# LoraWAN_Node.net
KiCad netlist of a schematic drawn in Altium Designer
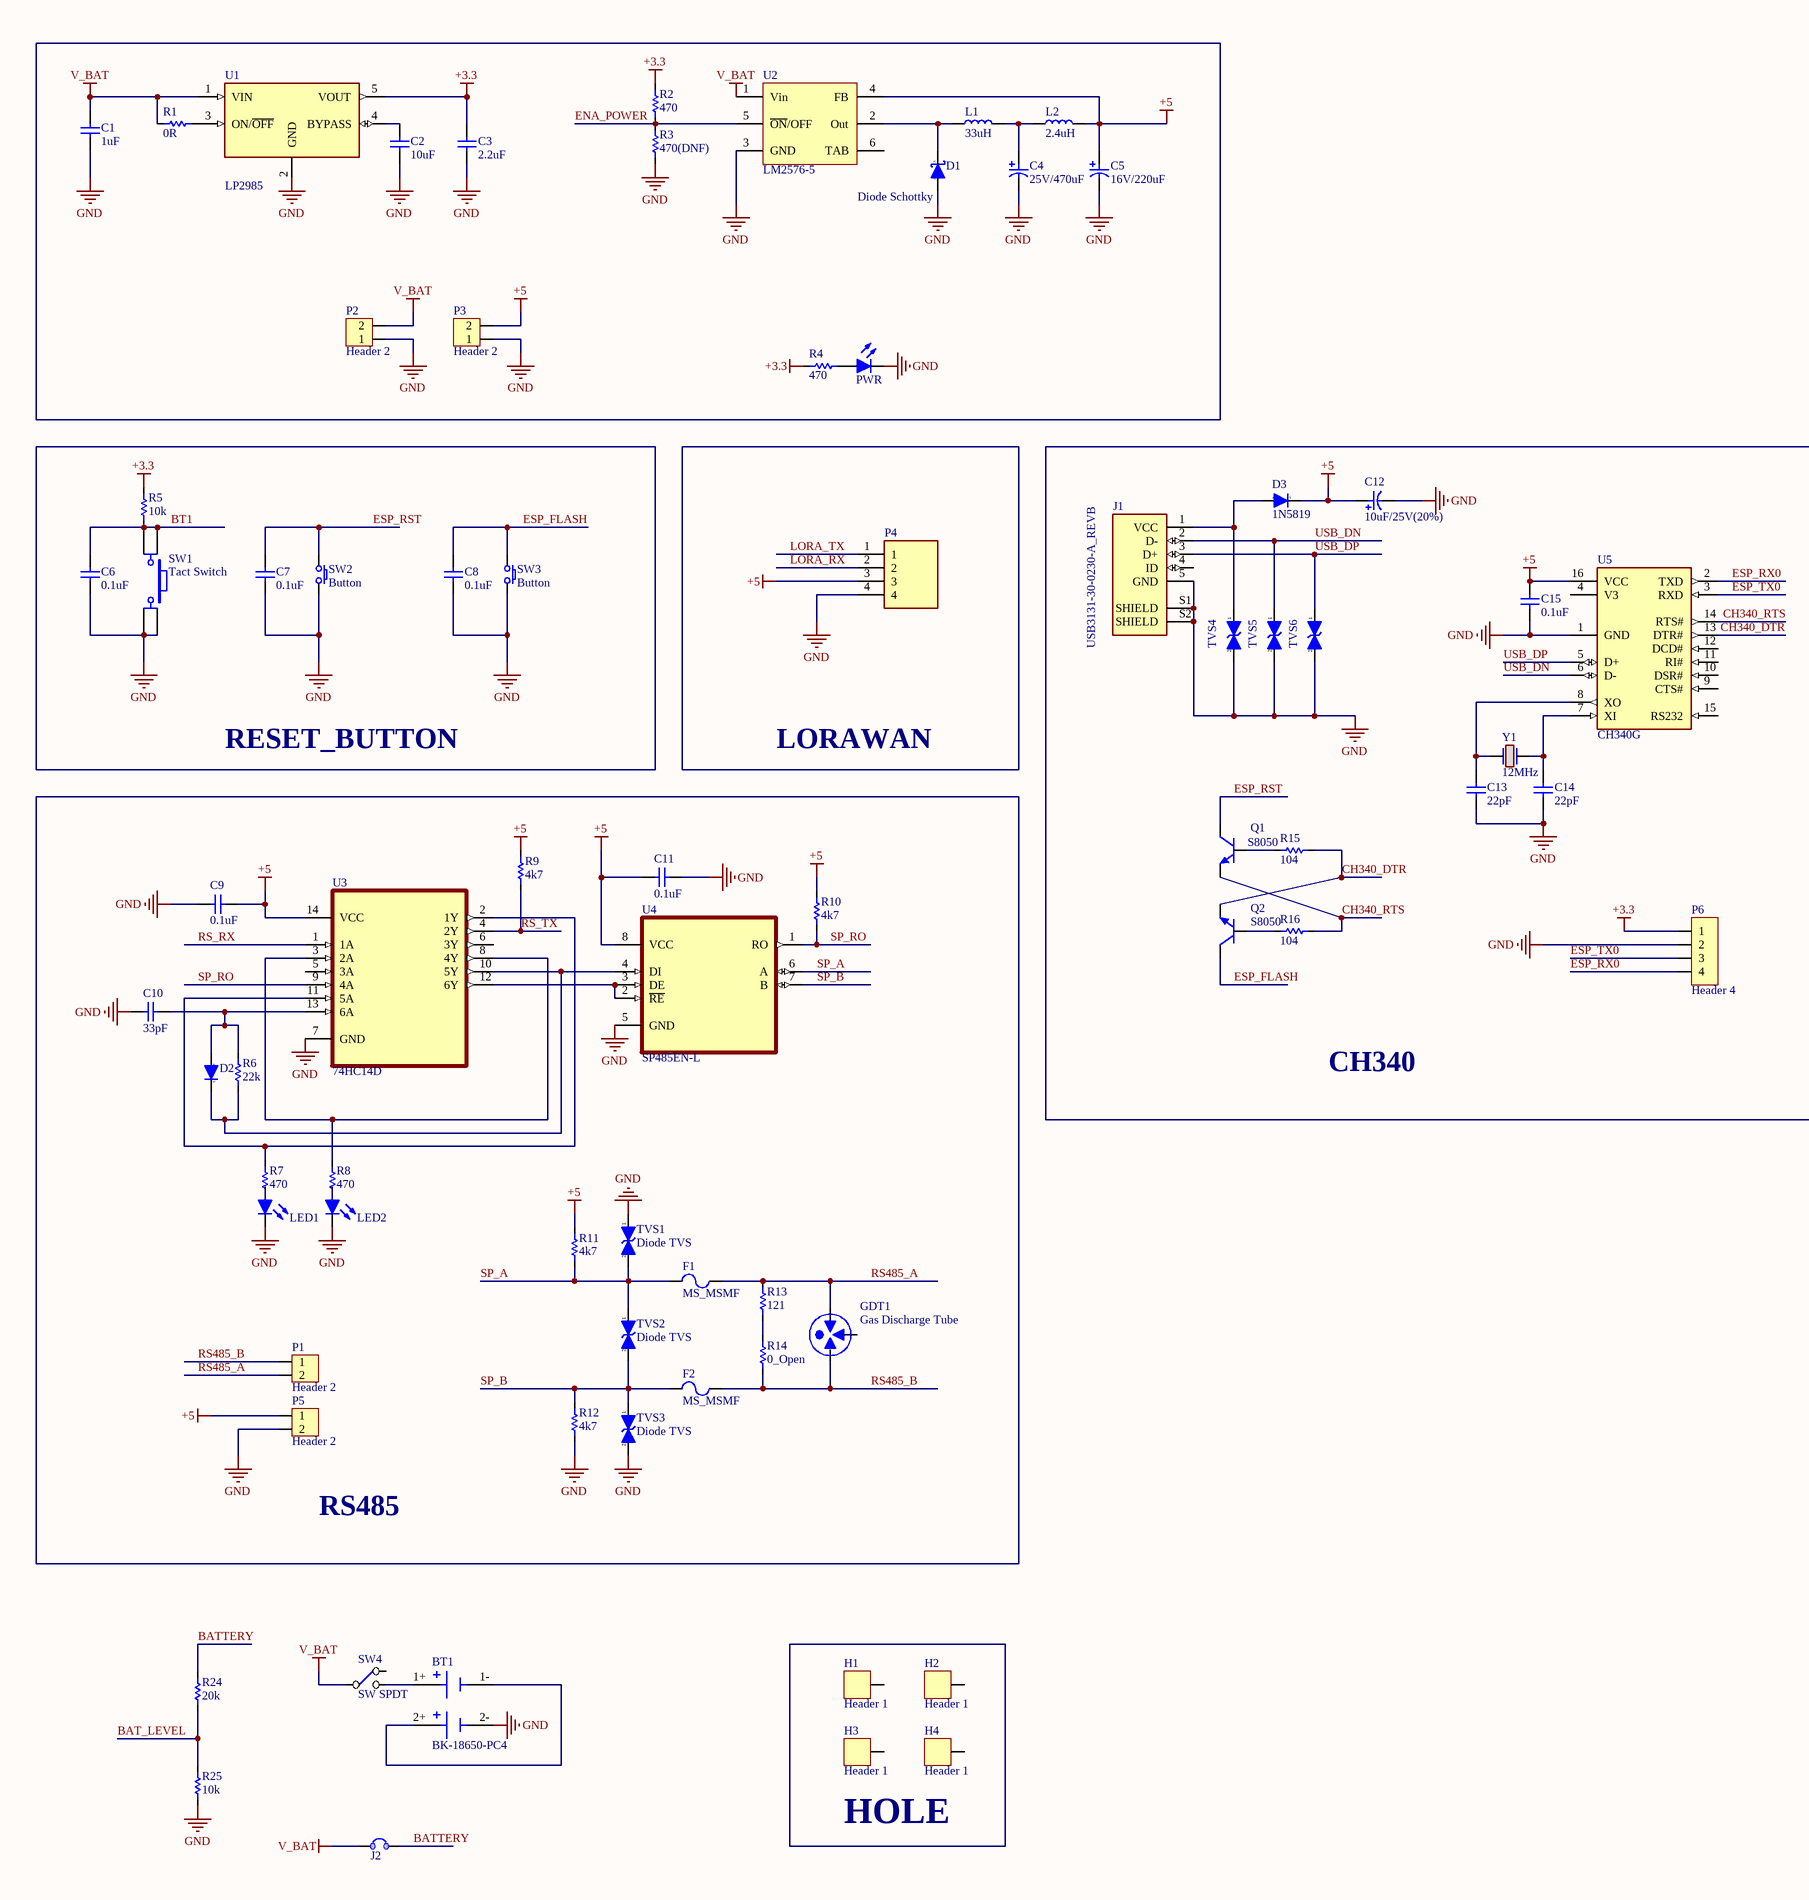
[diagram p0: LoraWAN_Node.SchDoc, left]
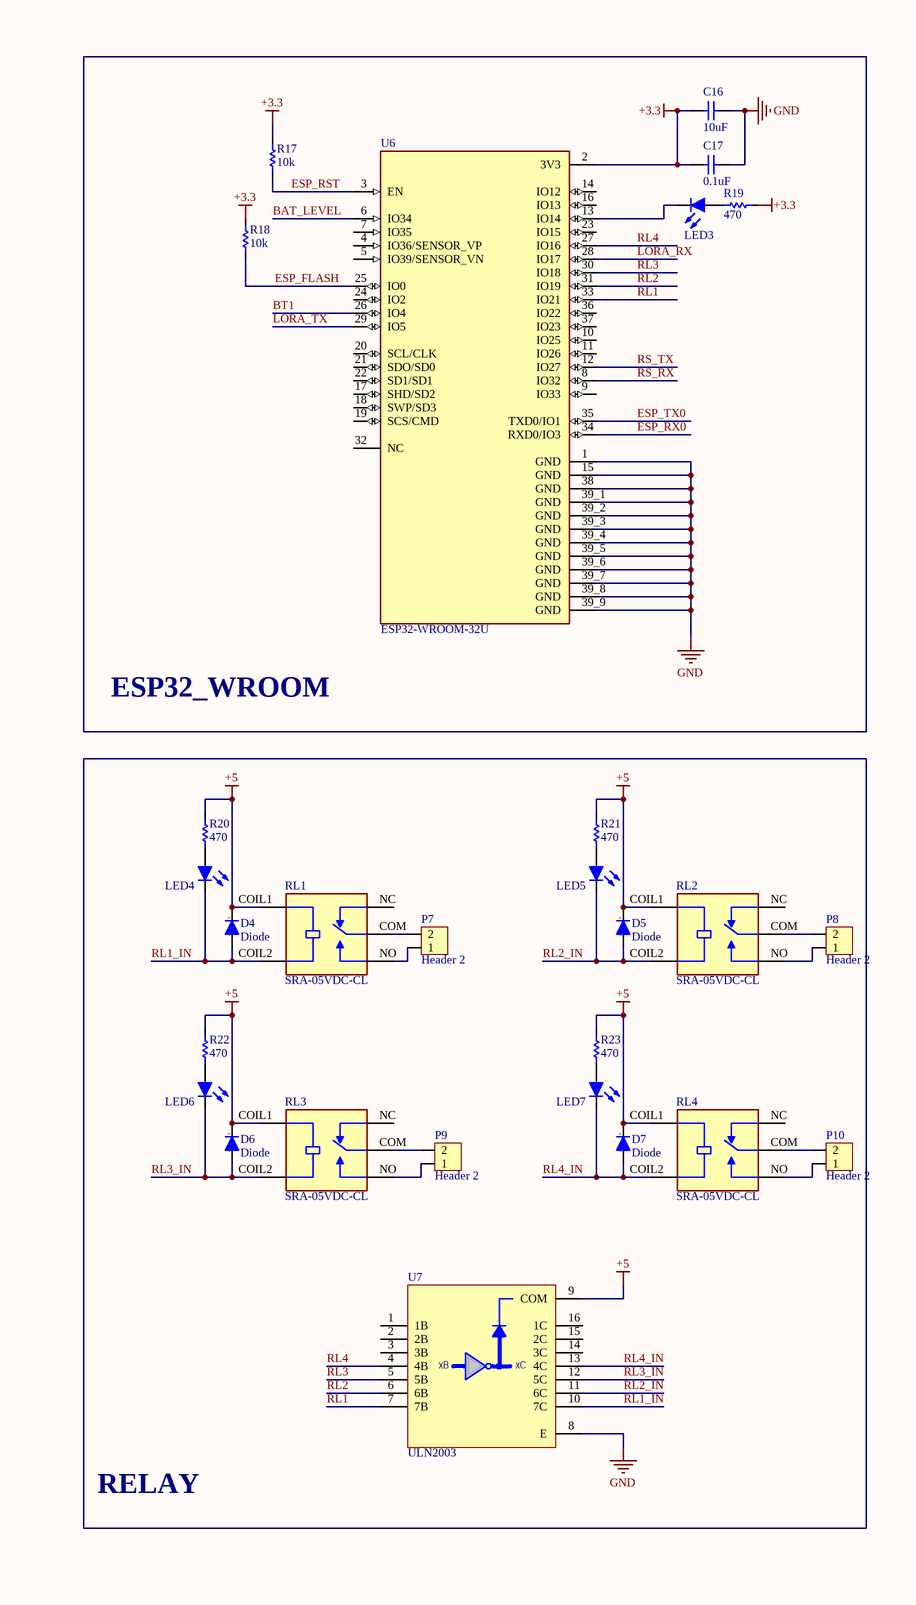
[diagram p1: LoraWAN_Node.SchDoc, right]

(export (version "E")
  (design (tool "Eeschema 10.0.6"))
  (components
    (comp (ref "BT1")
      (value "BK-18650-PC4")
      (footprint "BAT_BK-18650-PC4")
      (description "Battery Holder (Open) 18650 2 Cell PC Pin")
      (libsource (lib "BK-18650-PC4") (part "BK-18650-PC4"))
    )
    (comp (ref "C1")
      (value "1uF")
      (footprint "C 0603 (1608)")
      (description "Capacitor non-pol")
      (libsource (lib "BKIT4U_LIB_NEW") (part "Capacitor NP"))
    )
    (comp (ref "C2")
      (value "10uF")
      (footprint "C 0603 (1608)")
      (description "Capacitor non-pol")
      (libsource (lib "BKIT4U_LIB_NEW") (part "Capacitor NP"))
    )
    (comp (ref "C3")
      (value "2.2uF")
      (footprint "C 0603 (1608)")
      (description "Capacitor non-pol")
      (libsource (lib "BKIT4U_LIB_NEW") (part "Capacitor NP"))
    )
    (comp (ref "C4")
      (value "25V/470uF")
      (footprint "C SMD ALU (G)")
      (description "Capacitor pol")
      (libsource (lib "BKIT4U_LIB_NEW") (part "Capacitor"))
    )
    (comp (ref "C5")
      (value "16V/220uF")
      (footprint "C SMD ALU (D8)")
      (description "Capacitor pol")
      (libsource (lib "BKIT4U_LIB_NEW") (part "Capacitor"))
    )
    (comp (ref "C6")
      (value "0.1uF")
      (footprint "C 0603 (1608)")
      (description "Capacitor non-pol")
      (libsource (lib "BKIT4U_LIB_NEW") (part "Capacitor NP"))
    )
    (comp (ref "C7")
      (value "0.1uF")
      (footprint "C 0603 (1608)")
      (description "Capacitor non-pol")
      (libsource (lib "BKIT4U_LIB_NEW") (part "Capacitor NP"))
    )
    (comp (ref "C8")
      (value "0.1uF")
      (footprint "C 0603 (1608)")
      (description "Capacitor non-pol")
      (libsource (lib "BKIT4U_LIB_NEW") (part "Capacitor NP"))
    )
    (comp (ref "C9")
      (value "0.1uF")
      (footprint "C 0603 (1608)")
      (description "Capacitor non-pol")
      (libsource (lib "BKIT4U_LIB_NEW") (part "Capacitor NP"))
    )
    (comp (ref "C10")
      (value "33pF")
      (footprint "C 0603 (1608)")
      (description "Capacitor non-pol")
      (libsource (lib "BKIT4U_LIB_NEW") (part "Capacitor NP"))
    )
    (comp (ref "C11")
      (value "0.1uF")
      (footprint "C 0603 (1608)")
      (description "Capacitor non-pol")
      (libsource (lib "BKIT4U_LIB_NEW") (part "Capacitor NP"))
    )
    (comp (ref "C12")
      (value "10uF/25V(20%)")
      (footprint "C SMD TAN 1206 (A)")
      (description "Capacitor pol")
      (libsource (lib "BKIT4U_LIB_NEW") (part "Capacitor"))
    )
    (comp (ref "C13")
      (value "22pF")
      (footprint "C 0603 (1608)")
      (description "Capacitor non-pol")
      (libsource (lib "BKIT4U_LIB_NEW") (part "Capacitor NP"))
    )
    (comp (ref "C14")
      (value "22pF")
      (footprint "C 0603 (1608)")
      (description "Capacitor non-pol")
      (libsource (lib "BKIT4U_LIB_NEW") (part "Capacitor NP"))
    )
    (comp (ref "C15")
      (value "0.1uF")
      (footprint "C 0603 (1608)")
      (description "Capacitor non-pol")
      (libsource (lib "BKIT4U_LIB_NEW") (part "Capacitor NP"))
    )
    (comp (ref "C16")
      (value "10uF")
      (footprint "C 0603 (1608)")
      (description "Capacitor non-pol")
      (libsource (lib "BKIT4U_LIB_NEW") (part "Capacitor NP"))
    )
    (comp (ref "C17")
      (value "0.1uF")
      (footprint "C 0603 (1608)")
      (description "Capacitor non-pol")
      (libsource (lib "BKIT4U_LIB_NEW") (part "Capacitor NP"))
    )
    (comp (ref "D1")
      (value "Diode Schottky")
      (footprint "DO-214AC (SMA)")
      (description "Schottky Diode")
      (libsource (lib "BKIT4U_LIB_NEW") (part "Diode Schottky"))
    )
    (comp (ref "D2")
      (value "Diode")
      (footprint "DO-214AC (SMA)")
      (description "Default Diode")
      (libsource (lib "BKIT4U_LIB_NEW") (part "Diode"))
    )
    (comp (ref "D3")
      (value "1N5819")
      (footprint "DO-214AC (SMA)")
      (description "Default Diode")
      (libsource (lib "BKIT4U_LIB_NEW") (part "Diode"))
    )
    (comp (ref "D4")
      (value "Diode")
      (footprint "DO-214AC (SMA)")
      (description "Default Diode")
      (libsource (lib "BKIT4U_LIB_NEW") (part "Diode"))
    )
    (comp (ref "D5")
      (value "Diode")
      (footprint "DO-214AC (SMA)")
      (description "Default Diode")
      (libsource (lib "BKIT4U_LIB_NEW") (part "Diode"))
    )
    (comp (ref "D6")
      (value "Diode")
      (footprint "DO-214AC (SMA)")
      (description "Default Diode")
      (libsource (lib "BKIT4U_LIB_NEW") (part "Diode"))
    )
    (comp (ref "D7")
      (value "Diode")
      (footprint "DO-214AC (SMA)")
      (description "Default Diode")
      (libsource (lib "BKIT4U_LIB_NEW") (part "Diode"))
    )
    (comp (ref "F1")
      (value "MS_MSMF")
      (footprint "Fuse 1812P050")
      (description "Fuse")
      (libsource (lib "BKIT4U_LIB_NEW") (part "Fuse"))
    )
    (comp (ref "F2")
      (value "MS_MSMF")
      (footprint "Fuse 1812P050")
      (description "Fuse")
      (libsource (lib "BKIT4U_LIB_NEW") (part "Fuse"))
    )
    (comp (ref "GDT1")
      (value "Gas Discharge Tube")
      (footprint "CAPC4532X110N")
      (libsource (lib "BKIT4U_LIB_NEW") (part "Gas Discharge Tube"))
    )
    (comp (ref "H1")
      (value "Header 1")
      (footprint "M3")
      (description "Header, 1-Pin")
      (libsource (lib "BKIT4U_LIB_NEW") (part "Header 1"))
    )
    (comp (ref "H2")
      (value "Header 1")
      (footprint "M3")
      (description "Header, 1-Pin")
      (libsource (lib "BKIT4U_LIB_NEW") (part "Header 1"))
    )
    (comp (ref "H3")
      (value "Header 1")
      (footprint "M3")
      (description "Header, 1-Pin")
      (libsource (lib "BKIT4U_LIB_NEW") (part "Header 1"))
    )
    (comp (ref "H4")
      (value "Header 1")
      (footprint "M3")
      (description "Header, 1-Pin")
      (libsource (lib "BKIT4U_LIB_NEW") (part "Header 1"))
    )
    (comp (ref "J1")
      (value "USB3131-30-0230-A_REVB")
      (footprint "GCT_USB3131-30-0230-A_REVB")
      (description "USB - micro B USB 2.0 Receptacle Connector 5 Position Through Hole")
      (libsource (lib "USB3131-30-0230-A_REVB") (part "USB3131-30-0230-A_REVB"))
    )
    (comp (ref "J2")
      (value "JUMP 2")
      (footprint "JUMP/2/SMD/D")
      (libsource (lib "chipfc_altium_libs") (part "JUMP 2"))
    )
    (comp (ref "L1")
      (value "33uH")
      (footprint "Inductor SMD 12x12x8")
      (description "Inductor")
      (libsource (lib "BKIT4U_LIB_NEW") (part "Inductor"))
    )
    (comp (ref "L2")
      (value "2.4uH")
      (footprint "Inductor SMD 5.2x5.8x4.5mm")
      (description "Inductor")
      (libsource (lib "BKIT4U_LIB_NEW") (part "Inductor"))
    )
    (comp (ref "LED1")
      (value "Led")
      (footprint "Led SMD 0805")
      (description "Typical LED")
      (libsource (lib "BKIT4U_LIB_NEW") (part "Led"))
    )
    (comp (ref "LED2")
      (value "Led")
      (footprint "Led SMD 0805")
      (description "Typical LED")
      (libsource (lib "BKIT4U_LIB_NEW") (part "Led"))
    )
    (comp (ref "LED3")
      (value "Led")
      (footprint "Led SMD 0805")
      (description "Typical LED")
      (libsource (lib "BKIT4U_LIB_NEW") (part "Led"))
    )
    (comp (ref "LED4")
      (value "Led")
      (footprint "Led SMD 0805")
      (description "Typical LED")
      (libsource (lib "BKIT4U_LIB_NEW") (part "Led"))
    )
    (comp (ref "LED5")
      (value "Led")
      (footprint "Led SMD 0805")
      (description "Typical LED")
      (libsource (lib "BKIT4U_LIB_NEW") (part "Led"))
    )
    (comp (ref "LED6")
      (value "Led")
      (footprint "Led SMD 0805")
      (description "Typical LED")
      (libsource (lib "BKIT4U_LIB_NEW") (part "Led"))
    )
    (comp (ref "LED7")
      (value "Led")
      (footprint "Led SMD 0805")
      (description "Typical LED")
      (libsource (lib "BKIT4U_LIB_NEW") (part "Led"))
    )
    (comp (ref "P1")
      (value "Header 2")
      (footprint "HDR Domino 2 - 5MM")
      (description "Header, 2-Pin")
      (libsource (lib "") (part "Header 2_2"))
    )
    (comp (ref "P2")
      (value "Header 2")
      (footprint "HDR Domino 2 - 5MM")
      (description "Header, 2-Pin")
      (libsource (lib "BKIT4U_LIB_NEW") (part "Header 2"))
    )
    (comp (ref "P3")
      (value "Header 2")
      (footprint "HDR Domino 2 - 5MM")
      (description "Header, 2-Pin")
      (libsource (lib "BKIT4U_LIB_NEW") (part "Header 2"))
    )
    (comp (ref "P4")
      (value "110990030")
      (footprint "SEEED_110990030")
      (fields (field (name "MF") "Seeed Technology"))
      (libsource (lib "110990030") (part "110990030"))
    )
    (comp (ref "P5")
      (value "Header 2")
      (footprint "HDR Domino 2 - 5MM")
      (description "Header, 2-Pin")
      (libsource (lib "") (part "Header 2_2"))
    )
    (comp (ref "P6")
      (value "Header 4")
      (footprint "Header 4")
      (description "Header, 4-Pin")
      (libsource (lib "BKIT4U_LIB_NEW") (part "Header 4"))
    )
    (comp (ref "P7")
      (value "Header 2")
      (footprint "HDR Domino 2 - 5MM")
      (description "Header, 2-Pin")
      (libsource (lib "") (part "Header 2_1"))
    )
    (comp (ref "P8")
      (value "Header 2")
      (footprint "HDR Domino 2 - 5MM")
      (description "Header, 2-Pin")
      (libsource (lib "") (part "Header 2_1"))
    )
    (comp (ref "P9")
      (value "Header 2")
      (footprint "HDR Domino 2 - 5MM")
      (description "Header, 2-Pin")
      (libsource (lib "") (part "Header 2_1"))
    )
    (comp (ref "P10")
      (value "Header 2")
      (footprint "HDR Domino 2 - 5MM")
      (description "Header, 2-Pin")
      (libsource (lib "") (part "Header 2_1"))
    )
    (comp (ref "PWR")
      (value "Led")
      (footprint "Led SMD 0805")
      (description "Typical LED")
      (libsource (lib "BKIT4U_LIB_NEW") (part "Led"))
    )
    (comp (ref "Q1")
      (value "S8050")
      (footprint "SOT-23")
      (description "NPN Bipolar Transistor")
      (libsource (lib "BKIT4U_LIB_NEW") (part "Transistor NPN"))
    )
    (comp (ref "Q2")
      (value "S8050")
      (footprint "SOT-23")
      (description "NPN Bipolar Transistor")
      (libsource (lib "BKIT4U_LIB_NEW") (part "Transistor NPN"))
    )
    (comp (ref "R1")
      (value "0R")
      (footprint "R 0603 (1608)")
      (description "Resistor")
      (libsource (lib "BKIT4U_LIB_NEW") (part "Resistor"))
    )
    (comp (ref "R2")
      (value "470")
      (footprint "R 0603 (1608)")
      (description "Resistor")
      (libsource (lib "BKIT4U_LIB_NEW") (part "Resistor"))
    )
    (comp (ref "R3")
      (value "470(DNF)")
      (footprint "R 0603 (1608)")
      (description "Resistor")
      (libsource (lib "BKIT4U_LIB_NEW") (part "Resistor"))
    )
    (comp (ref "R4")
      (value "470")
      (footprint "R 0603 (1608)")
      (description "Resistor")
      (libsource (lib "BKIT4U_LIB_NEW") (part "Resistor"))
    )
    (comp (ref "R5")
      (value "10k")
      (footprint "R 0603 (1608)")
      (description "Resistor")
      (libsource (lib "BKIT4U_LIB_NEW") (part "Resistor"))
    )
    (comp (ref "R6")
      (value "22k")
      (footprint "R 0603 (1608)")
      (description "Resistor")
      (libsource (lib "BKIT4U_LIB_NEW") (part "Resistor"))
    )
    (comp (ref "R7")
      (value "470")
      (footprint "R 0603 (1608)")
      (description "Resistor")
      (libsource (lib "BKIT4U_LIB_NEW") (part "Resistor"))
    )
    (comp (ref "R8")
      (value "470")
      (footprint "R 0603 (1608)")
      (description "Resistor")
      (libsource (lib "BKIT4U_LIB_NEW") (part "Resistor"))
    )
    (comp (ref "R9")
      (value "4k7")
      (footprint "R 0603 (1608)")
      (description "Resistor")
      (libsource (lib "BKIT4U_LIB_NEW") (part "Resistor"))
    )
    (comp (ref "R10")
      (value "4k7")
      (footprint "R 0603 (1608)")
      (description "Resistor")
      (libsource (lib "BKIT4U_LIB_NEW") (part "Resistor"))
    )
    (comp (ref "R11")
      (value "4k7")
      (footprint "R 0603 (1608)")
      (description "Resistor")
      (libsource (lib "BKIT4U_LIB_NEW") (part "Resistor"))
    )
    (comp (ref "R12")
      (value "4k7")
      (footprint "R 0603 (1608)")
      (description "Resistor")
      (libsource (lib "BKIT4U_LIB_NEW") (part "Resistor"))
    )
    (comp (ref "R13")
      (value "121")
      (footprint "R 0603 (1608)")
      (description "Resistor")
      (libsource (lib "BKIT4U_LIB_NEW") (part "Resistor"))
    )
    (comp (ref "R14")
      (value "0_Open")
      (footprint "R 0603 (1608)")
      (description "Resistor")
      (libsource (lib "BKIT4U_LIB_NEW") (part "Resistor"))
    )
    (comp (ref "R15")
      (value "104")
      (footprint "R 0603 (1608)")
      (description "Resistor")
      (libsource (lib "BKIT4U_LIB_NEW") (part "Resistor"))
    )
    (comp (ref "R16")
      (value "104")
      (footprint "R 0603 (1608)")
      (description "Resistor")
      (libsource (lib "BKIT4U_LIB_NEW") (part "Resistor"))
    )
    (comp (ref "R17")
      (value "10k")
      (footprint "R 0603 (1608)")
      (description "Resistor")
      (libsource (lib "BKIT4U_LIB_NEW") (part "Resistor"))
    )
    (comp (ref "R18")
      (value "10k")
      (footprint "R 0603 (1608)")
      (description "Resistor")
      (libsource (lib "BKIT4U_LIB_NEW") (part "Resistor"))
    )
    (comp (ref "R19")
      (value "470")
      (footprint "R 0603 (1608)")
      (description "Resistor")
      (libsource (lib "BKIT4U_LIB_NEW") (part "Resistor"))
    )
    (comp (ref "R20")
      (value "470")
      (footprint "R 0603 (1608)")
      (description "Resistor")
      (libsource (lib "BKIT4U_LIB_NEW") (part "Resistor"))
    )
    (comp (ref "R21")
      (value "470")
      (footprint "R 0603 (1608)")
      (description "Resistor")
      (libsource (lib "BKIT4U_LIB_NEW") (part "Resistor"))
    )
    (comp (ref "R22")
      (value "470")
      (footprint "R 0603 (1608)")
      (description "Resistor")
      (libsource (lib "BKIT4U_LIB_NEW") (part "Resistor"))
    )
    (comp (ref "R23")
      (value "470")
      (footprint "R 0603 (1608)")
      (description "Resistor")
      (libsource (lib "BKIT4U_LIB_NEW") (part "Resistor"))
    )
    (comp (ref "R24")
      (value "20k")
      (footprint "R 0603 (1608)")
      (description "Resistor")
      (libsource (lib "BKIT4U_LIB_NEW") (part "Resistor"))
    )
    (comp (ref "R25")
      (value "10k")
      (footprint "R 0603 (1608)")
      (description "Resistor")
      (libsource (lib "BKIT4U_LIB_NEW") (part "Resistor"))
    )
    (comp (ref "RL1")
      (value "SRA-05VDC-CL")
      (footprint "RELAY_SRA-05VDC-CL")
      (fields (field (name "MF") "Songle Relay"))
      (libsource (lib "SRA-05VDC-CL") (part "SRA-05VDC-CL"))
    )
    (comp (ref "RL2")
      (value "SRA-05VDC-CL")
      (footprint "RELAY_SRA-05VDC-CL")
      (fields (field (name "MF") "Songle Relay"))
      (libsource (lib "SRA-05VDC-CL") (part "SRA-05VDC-CL"))
    )
    (comp (ref "RL3")
      (value "SRA-05VDC-CL")
      (footprint "RELAY_SRA-05VDC-CL")
      (fields (field (name "MF") "Songle Relay"))
      (libsource (lib "SRA-05VDC-CL") (part "SRA-05VDC-CL"))
    )
    (comp (ref "RL4")
      (value "SRA-05VDC-CL")
      (footprint "RELAY_SRA-05VDC-CL")
      (fields (field (name "MF") "Songle Relay"))
      (libsource (lib "SRA-05VDC-CL") (part "SRA-05VDC-CL"))
    )
    (comp (ref "SW1")
      (value "Tact Switch")
      (footprint "SW/4/DIP/SMALL")
      (description "Tact switch 4 pin")
      (libsource (lib "BKIT4U_LIB_NEW") (part "SW SPST-4"))
    )
    (comp (ref "SW2")
      (value "Button")
      (footprint "SW/2/SMD")
      (description "Tact switch 2 pin")
      (libsource (lib "BKIT4U_LIB_NEW") (part "SW SPST"))
    )
    (comp (ref "SW3")
      (value "Button")
      (footprint "SW/2/SMD")
      (description "Tact switch 2 pin")
      (libsource (lib "BKIT4U_LIB_NEW") (part "SW SPST"))
    )
    (comp (ref "SW4")
      (value "SW SPDT")
      (footprint "SW/3/SPDT/SS12D10")
      (libsource (lib "chipfc_altium_libs") (part "SW SPDT"))
    )
    (comp (ref "TVS1")
      (value "Diode TVS")
      (footprint "DO-214AA (SMB)")
      (description "Bi-directional TVS Diode")
      (libsource (lib "BKIT4U_LIB_NEW") (part "Diode TVS Bi-Dir"))
    )
    (comp (ref "TVS2")
      (value "Diode TVS")
      (footprint "DO-214AA (SMB)")
      (description "Bi-directional TVS Diode")
      (libsource (lib "BKIT4U_LIB_NEW") (part "Diode TVS Bi-Dir"))
    )
    (comp (ref "TVS3")
      (value "Diode TVS")
      (footprint "DO-214AA (SMB)")
      (description "Bi-directional TVS Diode")
      (libsource (lib "BKIT4U_LIB_NEW") (part "Diode TVS Bi-Dir"))
    )
    (comp (ref "TVS4")
      (value "Diode TVS")
      (footprint "DO-214AC (SMA)")
      (description "Bi-directional TVS Diode")
      (libsource (lib "BKIT4U_LIB_NEW") (part "Diode TVS Bi-Dir"))
    )
    (comp (ref "TVS5")
      (value "Diode TVS")
      (footprint "DO-214AC (SMA)")
      (description "Bi-directional TVS Diode")
      (libsource (lib "BKIT4U_LIB_NEW") (part "Diode TVS Bi-Dir"))
    )
    (comp (ref "TVS6")
      (value "Diode TVS")
      (footprint "DO-214AC (SMA)")
      (description "Bi-directional TVS Diode")
      (libsource (lib "BKIT4U_LIB_NEW") (part "Diode TVS Bi-Dir"))
    )
    (comp (ref "U1")
      (value "LP2985")
      (footprint "SOT-23-5")
      (libsource (lib "BKIT4U_LIB_NEW") (part "LP2985"))
    )
    (comp (ref "U2")
      (value "LM2576-5")
      (footprint "TO-263-5")
      (description "SIMPLE SWITCHER® 3A Step-Down Voltage Regulator")
      (libsource (lib "BKIT4U_LIB_NEW") (part "LM2576/96"))
    )
    (comp (ref "U3")
      (value "74HC14D")
      (footprint "SOIC127P600X175-14N")
      (description "Inverter IC 6 Channel Schmitt Trigger 14-SOIC")
      (fields (field (name "MF") "Toshiba"))
      (libsource (lib "74HC14D") (part "74HC14D"))
    )
    (comp (ref "U4")
      (value "SP485EN-L")
      (footprint "SOIC-8")
      (description "SP485 Series 5 Mbps 5 V Low Power Half Duplex RS-485 Transceiver - NSOIC-8")
      (fields (field (name "MF") "MaxLinear, Inc."))
      (libsource (lib "SP485EN-L") (part "SP485EN-L"))
    )
    (comp (ref "U5")
      (value "CH340G")
      (footprint "SOIC-16")
      (libsource (lib "BKIT4U_LIB_NEW") (part "CH340G"))
    )
    (comp (ref "U6")
      (value "ESP32-WROOM-32U")
      (footprint "XCVR_ESP32-WROOM-32U")
      (fields (field (name "MF") "Espressif Systems"))
      (libsource (lib "ESP32-WROOM-32U") (part "ESP32-WROOM-32U"))
    )
    (comp (ref "U7")
      (value "ULN2003")
      (footprint "SOIC-16")
      (description "High-voltage, high-current Darlington transistor arrays")
      (libsource (lib "BKIT4U_LIB_NEW") (part "ULN2003"))
    )
    (comp (ref "Y1")
      (value "12MHz")
      (footprint "Crystal HC49S DIP")
      (libsource (lib "BKIT4U_LIB_NEW") (part "Crystal"))
    )
  )
  (nets
    (net (code "1") (name "+3.3") (class "Default")
      (node (ref "C16") (pin "1") (pinfunction "1_1") (pintype "passive"))
      (node (ref "C17") (pin "1") (pinfunction "1_1") (pintype "passive"))
      (node (ref "C3") (pin "1") (pinfunction "1_1") (pintype "passive"))
      (node (ref "P6") (pin "1") (pinfunction "1_1") (pintype "passive"))
      (node (ref "R17") (pin "2") (pinfunction "2_2") (pintype "passive"))
      (node (ref "R18") (pin "2") (pinfunction "2_2") (pintype "passive"))
      (node (ref "R19") (pin "2") (pinfunction "2_2") (pintype "passive"))
      (node (ref "R2") (pin "1") (pinfunction "1_1") (pintype "passive"))
      (node (ref "R4") (pin "2") (pinfunction "2_2") (pintype "passive"))
      (node (ref "R5") (pin "2") (pinfunction "2_2") (pintype "passive"))
      (node (ref "U1") (pin "5") (pinfunction "VOUT_5") (pintype "output"))
      (node (ref "U6") (pin "2") (pinfunction "3V3_2") (pintype "power_in"))
    )
    (net (code "2") (name "+5") (class "Default")
      (node (ref "C11") (pin "1") (pinfunction "1_1") (pintype "passive"))
      (node (ref "C12") (pin "1") (pinfunction "1_1") (pintype "passive"))
      (node (ref "C15") (pin "2") (pinfunction "2_2") (pintype "passive"))
      (node (ref "C5") (pin "1") (pinfunction "1_1") (pintype "passive"))
      (node (ref "C9") (pin "2") (pinfunction "2_2") (pintype "passive"))
      (node (ref "D3") (pin "1") (pinfunction "Cathode_1") (pintype "passive"))
      (node (ref "D4") (pin "1") (pinfunction "Cathode_1") (pintype "passive"))
      (node (ref "D5") (pin "1") (pinfunction "Cathode_1") (pintype "passive"))
      (node (ref "D6") (pin "1") (pinfunction "Cathode_1") (pintype "passive"))
      (node (ref "D7") (pin "1") (pinfunction "Cathode_1") (pintype "passive"))
      (node (ref "L2") (pin "2") (pinfunction "2_2") (pintype "passive"))
      (node (ref "P3") (pin "2") (pinfunction "2_2") (pintype "passive"))
      (node (ref "P4") (pin "3") (pinfunction "3_3") (pintype "passive"))
      (node (ref "P5") (pin "1") (pinfunction "1_1") (pintype "passive"))
      (node (ref "R10") (pin "2") (pinfunction "2_2") (pintype "passive"))
      (node (ref "R11") (pin "2") (pinfunction "2_2") (pintype "passive"))
      (node (ref "R20") (pin "2") (pinfunction "2_2") (pintype "passive"))
      (node (ref "R21") (pin "2") (pinfunction "2_2") (pintype "passive"))
      (node (ref "R22") (pin "2") (pinfunction "2_2") (pintype "passive"))
      (node (ref "R23") (pin "2") (pinfunction "2_2") (pintype "passive"))
      (node (ref "R9") (pin "2") (pinfunction "2_2") (pintype "passive"))
      (node (ref "RL1") (pin "COIL1") (pinfunction "COIL1_COIL1") (pintype "passive"))
      (node (ref "RL2") (pin "COIL1") (pinfunction "COIL1_COIL1") (pintype "passive"))
      (node (ref "RL3") (pin "COIL1") (pinfunction "COIL1_COIL1") (pintype "passive"))
      (node (ref "RL4") (pin "COIL1") (pinfunction "COIL1_COIL1") (pintype "passive"))
      (node (ref "U2") (pin "4") (pinfunction "FB_4") (pintype "passive"))
      (node (ref "U3") (pin "14") (pinfunction "VCC_14") (pintype "power_in"))
      (node (ref "U4") (pin "8") (pinfunction "VCC_8") (pintype "power_in"))
      (node (ref "U5") (pin "16") (pinfunction "VCC_16") (pintype "power_in"))
      (node (ref "U7") (pin "9") (pinfunction "COM_9") (pintype "passive"))
    )
    (net (code "3") (name "/BATTERY") (class "Default")
      (node (ref "J2") (pin "2") (pinfunction "2_2") (pintype "passive"))
      (node (ref "R24") (pin "2") (pinfunction "2_2") (pintype "passive"))
    )
    (net (code "4") (name "/BAT_LEVEL") (class "Default")
      (node (ref "R24") (pin "1") (pinfunction "1_1") (pintype "passive"))
      (node (ref "R25") (pin "2") (pinfunction "2_2") (pintype "passive"))
      (node (ref "U6") (pin "6") (pinfunction "IO34_6") (pintype "input"))
    )
    (net (code "5") (name "/BT1") (class "Default")
      (node (ref "C6") (pin "1") (pinfunction "1_1") (pintype "passive"))
      (node (ref "R5") (pin "1") (pinfunction "1_1") (pintype "passive"))
      (node (ref "SW1") (pin "1") (pinfunction "1_1") (pintype "passive"))
      (node (ref "SW1") (pin "4") (pinfunction "2_4") (pintype "passive"))
      (node (ref "U6") (pin "26") (pinfunction "IO4_26") (pintype "bidirectional"))
    )
    (net (code "6") (name "/CH340_DTR") (class "Default")
      (node (ref "Q2") (pin "2") (pinfunction "E_2") (pintype "passive"))
      (node (ref "R15") (pin "2") (pinfunction "2_2") (pintype "passive"))
      (node (ref "U5") (pin "13") (pinfunction "DTR#_13") (pintype "output"))
    )
    (net (code "7") (name "/CH340_RTS") (class "Default")
      (node (ref "Q1") (pin "2") (pinfunction "E_2") (pintype "passive"))
      (node (ref "R16") (pin "2") (pinfunction "2_2") (pintype "passive"))
      (node (ref "U5") (pin "14") (pinfunction "RTS#_14") (pintype "output"))
    )
    (net (code "8") (name "/ENA_POWER") (class "Default")
      (node (ref "R2") (pin "2") (pinfunction "2_2") (pintype "passive"))
      (node (ref "R3") (pin "1") (pinfunction "1_1") (pintype "passive"))
      (node (ref "U2") (pin "5") (pinfunction "~{ON}/OFF_5") (pintype "passive"))
    )
    (net (code "9") (name "/ESP_FLASH") (class "Default")
      (node (ref "C8") (pin "1") (pinfunction "1_1") (pintype "passive"))
      (node (ref "Q2") (pin "3") (pinfunction "C_3") (pintype "passive"))
      (node (ref "R18") (pin "1") (pinfunction "1_1") (pintype "passive"))
      (node (ref "SW3") (pin "1") (pinfunction "1_1") (pintype "passive"))
      (node (ref "U6") (pin "25") (pinfunction "IO0_25") (pintype "bidirectional"))
    )
    (net (code "10") (name "/ESP_RST") (class "Default")
      (node (ref "C7") (pin "1") (pinfunction "1_1") (pintype "passive"))
      (node (ref "Q1") (pin "3") (pinfunction "C_3") (pintype "passive"))
      (node (ref "R17") (pin "1") (pinfunction "1_1") (pintype "passive"))
      (node (ref "SW2") (pin "1") (pinfunction "1_1") (pintype "passive"))
      (node (ref "U6") (pin "3") (pinfunction "EN_3") (pintype "input"))
    )
    (net (code "11") (name "/ESP_RX0") (class "Default")
      (node (ref "P6") (pin "4") (pinfunction "4_4") (pintype "passive"))
      (node (ref "U5") (pin "2") (pinfunction "TXD_2") (pintype "output"))
      (node (ref "U6") (pin "34") (pinfunction "RXD0/IO3_34") (pintype "bidirectional"))
    )
    (net (code "12") (name "/ESP_TX0") (class "Default")
      (node (ref "P6") (pin "3") (pinfunction "3_3") (pintype "passive"))
      (node (ref "U5") (pin "3") (pinfunction "RXD_3") (pintype "input"))
      (node (ref "U6") (pin "35") (pinfunction "TXD0/IO1_35") (pintype "bidirectional"))
    )
    (net (code "13") (name "/LORA_RX") (class "Default")
      (node (ref "P4") (pin "2") (pinfunction "2_2") (pintype "passive"))
      (node (ref "U6") (pin "28") (pinfunction "IO17_28") (pintype "bidirectional"))
    )
    (net (code "14") (name "/LORA_TX") (class "Default")
      (node (ref "P4") (pin "1") (pinfunction "1_1") (pintype "passive"))
      (node (ref "U6") (pin "29") (pinfunction "IO5_29") (pintype "bidirectional"))
    )
    (net (code "15") (name "/RL1") (class "Default")
      (node (ref "U6") (pin "33") (pinfunction "IO21_33") (pintype "bidirectional"))
      (node (ref "U7") (pin "7") (pinfunction "7B_7") (pintype "passive"))
    )
    (net (code "16") (name "/RL1_IN") (class "Default")
      (node (ref "D4") (pin "2") (pinfunction "Anode_2") (pintype "passive"))
      (node (ref "LED4") (pin "1") (pinfunction "K_1") (pintype "passive"))
      (node (ref "RL1") (pin "COIL2") (pinfunction "COIL2_COIL2") (pintype "passive"))
      (node (ref "U7") (pin "10") (pinfunction "7C_10") (pintype "passive"))
    )
    (net (code "17") (name "/RL2") (class "Default")
      (node (ref "U6") (pin "31") (pinfunction "IO19_31") (pintype "bidirectional"))
      (node (ref "U7") (pin "6") (pinfunction "6B_6") (pintype "passive"))
    )
    (net (code "18") (name "/RL2_IN") (class "Default")
      (node (ref "D5") (pin "2") (pinfunction "Anode_2") (pintype "passive"))
      (node (ref "LED5") (pin "1") (pinfunction "K_1") (pintype "passive"))
      (node (ref "RL2") (pin "COIL2") (pinfunction "COIL2_COIL2") (pintype "passive"))
      (node (ref "U7") (pin "11") (pinfunction "6C_11") (pintype "passive"))
    )
    (net (code "19") (name "/RL3") (class "Default")
      (node (ref "U6") (pin "30") (pinfunction "IO18_30") (pintype "bidirectional"))
      (node (ref "U7") (pin "5") (pinfunction "5B_5") (pintype "passive"))
    )
    (net (code "20") (name "/RL3_IN") (class "Default")
      (node (ref "D6") (pin "2") (pinfunction "Anode_2") (pintype "passive"))
      (node (ref "LED6") (pin "1") (pinfunction "K_1") (pintype "passive"))
      (node (ref "RL3") (pin "COIL2") (pinfunction "COIL2_COIL2") (pintype "passive"))
      (node (ref "U7") (pin "12") (pinfunction "5C_12") (pintype "passive"))
    )
    (net (code "21") (name "/RL4") (class "Default")
      (node (ref "U6") (pin "27") (pinfunction "IO16_27") (pintype "bidirectional"))
      (node (ref "U7") (pin "4") (pinfunction "4B_4") (pintype "passive"))
    )
    (net (code "22") (name "/RL4_IN") (class "Default")
      (node (ref "D7") (pin "2") (pinfunction "Anode_2") (pintype "passive"))
      (node (ref "LED7") (pin "1") (pinfunction "K_1") (pintype "passive"))
      (node (ref "RL4") (pin "COIL2") (pinfunction "COIL2_COIL2") (pintype "passive"))
      (node (ref "U7") (pin "13") (pinfunction "4C_13") (pintype "passive"))
    )
    (net (code "23") (name "/RS485_A") (class "Default")
      (node (ref "F1") (pin "2") (pinfunction "2_2") (pintype "passive"))
      (node (ref "GDT1") (pin "1") (pinfunction "1_1") (pintype "passive"))
      (node (ref "P1") (pin "2") (pinfunction "2_2") (pintype "passive"))
      (node (ref "R13") (pin "1") (pinfunction "1_1") (pintype "passive"))
    )
    (net (code "24") (name "/RS485_B") (class "Default")
      (node (ref "F2") (pin "2") (pinfunction "2_2") (pintype "passive"))
      (node (ref "GDT1") (pin "2") (pinfunction "2_2") (pintype "passive"))
      (node (ref "P1") (pin "1") (pinfunction "1_1") (pintype "passive"))
      (node (ref "R14") (pin "2") (pinfunction "2_2") (pintype "passive"))
    )
    (net (code "25") (name "/RS_RX") (class "Default")
      (node (ref "U3") (pin "1") (pinfunction "1A_1") (pintype "input"))
      (node (ref "U6") (pin "8") (pinfunction "IO32_8") (pintype "bidirectional"))
    )
    (net (code "26") (name "/RS_TX") (class "Default")
      (node (ref "R9") (pin "1") (pinfunction "1_1") (pintype "passive"))
      (node (ref "U3") (pin "4") (pinfunction "2Y_4") (pintype "output"))
      (node (ref "U6") (pin "12") (pinfunction "IO27_12") (pintype "bidirectional"))
    )
    (net (code "27") (name "/SP_A") (class "Default")
      (node (ref "F1") (pin "1") (pinfunction "1_1") (pintype "passive"))
      (node (ref "R11") (pin "1") (pinfunction "1_1") (pintype "passive"))
      (node (ref "TVS1") (pin "2") (pinfunction "K_2") (pintype "passive"))
      (node (ref "TVS2") (pin "1") (pinfunction "A_1") (pintype "passive"))
      (node (ref "U4") (pin "6") (pinfunction "A_6") (pintype "bidirectional"))
    )
    (net (code "28") (name "/SP_B") (class "Default")
      (node (ref "F2") (pin "1") (pinfunction "1_1") (pintype "passive"))
      (node (ref "R12") (pin "2") (pinfunction "2_2") (pintype "passive"))
      (node (ref "TVS2") (pin "2") (pinfunction "K_2") (pintype "passive"))
      (node (ref "TVS3") (pin "1") (pinfunction "A_1") (pintype "passive"))
      (node (ref "U4") (pin "7") (pinfunction "B_7") (pintype "bidirectional"))
    )
    (net (code "29") (name "/SP_RO") (class "Default")
      (node (ref "R10") (pin "1") (pinfunction "1_1") (pintype "passive"))
      (node (ref "U3") (pin "9") (pinfunction "4A_9") (pintype "input"))
      (node (ref "U4") (pin "1") (pinfunction "RO_1") (pintype "output"))
    )
    (net (code "30") (name "/USB_DN") (class "Default")
      (node (ref "J1") (pin "2") (pinfunction "D-_2") (pintype "bidirectional"))
      (node (ref "TVS5") (pin "1") (pinfunction "A_1") (pintype "passive"))
      (node (ref "U5") (pin "6") (pinfunction "D-_6") (pintype "bidirectional"))
    )
    (net (code "31") (name "/USB_DP") (class "Default")
      (node (ref "J1") (pin "3") (pinfunction "D+_3") (pintype "bidirectional"))
      (node (ref "TVS6") (pin "1") (pinfunction "A_1") (pintype "passive"))
      (node (ref "U5") (pin "5") (pinfunction "D+_5") (pintype "bidirectional"))
    )
    (net (code "32") (name "GND") (class "Default")
      (node (ref "BT1") (pin "2-") (pinfunction "2-_2-") (pintype "passive"))
      (node (ref "C1") (pin "2") (pinfunction "2_2") (pintype "passive"))
      (node (ref "C10") (pin "1") (pinfunction "1_1") (pintype "passive"))
      (node (ref "C11") (pin "2") (pinfunction "2_2") (pintype "passive"))
      (node (ref "C12") (pin "2") (pinfunction "2_2") (pintype "passive"))
      (node (ref "C13") (pin "2") (pinfunction "2_2") (pintype "passive"))
      (node (ref "C14") (pin "2") (pinfunction "2_2") (pintype "passive"))
      (node (ref "C15") (pin "1") (pinfunction "1_1") (pintype "passive"))
      (node (ref "C16") (pin "2") (pinfunction "2_2") (pintype "passive"))
      (node (ref "C17") (pin "2") (pinfunction "2_2") (pintype "passive"))
      (node (ref "C2") (pin "2") (pinfunction "2_2") (pintype "passive"))
      (node (ref "C3") (pin "2") (pinfunction "2_2") (pintype "passive"))
      (node (ref "C4") (pin "2") (pinfunction "2_2") (pintype "passive"))
      (node (ref "C5") (pin "2") (pinfunction "2_2") (pintype "passive"))
      (node (ref "C6") (pin "2") (pinfunction "2_2") (pintype "passive"))
      (node (ref "C7") (pin "2") (pinfunction "2_2") (pintype "passive"))
      (node (ref "C8") (pin "2") (pinfunction "2_2") (pintype "passive"))
      (node (ref "C9") (pin "1") (pinfunction "1_1") (pintype "passive"))
      (node (ref "D1") (pin "2") (pinfunction "K_2") (pintype "passive"))
      (node (ref "J1") (pin "5") (pinfunction "GND_5") (pintype "power_in"))
      (node (ref "J1") (pin "S1") (pinfunction "SHIELD_S1") (pintype "passive"))
      (node (ref "J1") (pin "S2") (pinfunction "SHIELD_S2") (pintype "passive"))
      (node (ref "LED1") (pin "1") (pinfunction "K_1") (pintype "passive"))
      (node (ref "LED2") (pin "1") (pinfunction "K_1") (pintype "passive"))
      (node (ref "P2") (pin "1") (pinfunction "1_1") (pintype "passive"))
      (node (ref "P3") (pin "1") (pinfunction "1_1") (pintype "passive"))
      (node (ref "P4") (pin "4") (pinfunction "4_4") (pintype "passive"))
      (node (ref "P5") (pin "2") (pinfunction "2_2") (pintype "passive"))
      (node (ref "P6") (pin "2") (pinfunction "2_2") (pintype "passive"))
      (node (ref "PWR") (pin "1") (pinfunction "K_1") (pintype "passive"))
      (node (ref "R12") (pin "1") (pinfunction "1_1") (pintype "passive"))
      (node (ref "R25") (pin "1") (pinfunction "1_1") (pintype "passive"))
      (node (ref "R3") (pin "2") (pinfunction "2_2") (pintype "passive"))
      (node (ref "SW1") (pin "2") (pinfunction "2_2") (pintype "passive"))
      (node (ref "SW1") (pin "3") (pinfunction "1_3") (pintype "passive"))
      (node (ref "SW2") (pin "2") (pinfunction "2_2") (pintype "passive"))
      (node (ref "SW3") (pin "2") (pinfunction "2_2") (pintype "passive"))
      (node (ref "TVS1") (pin "1") (pinfunction "A_1") (pintype "passive"))
      (node (ref "TVS3") (pin "2") (pinfunction "K_2") (pintype "passive"))
      (node (ref "TVS4") (pin "2") (pinfunction "K_2") (pintype "passive"))
      (node (ref "TVS5") (pin "2") (pinfunction "K_2") (pintype "passive"))
      (node (ref "TVS6") (pin "2") (pinfunction "K_2") (pintype "passive"))
      (node (ref "U1") (pin "2") (pinfunction "GND_2") (pintype "passive"))
      (node (ref "U2") (pin "3") (pinfunction "GND_3") (pintype "passive"))
      (node (ref "U3") (pin "7") (pinfunction "GND_7") (pintype "passive"))
      (node (ref "U4") (pin "5") (pinfunction "GND_5") (pintype "passive"))
      (node (ref "U5") (pin "1") (pinfunction "GND_1") (pintype "power_in"))
      (node (ref "U6") (pin "1") (pinfunction "GND_1") (pintype "power_in"))
      (node (ref "U6") (pin "15") (pinfunction "GND_15") (pintype "power_in"))
      (node (ref "U6") (pin "38") (pinfunction "GND_38") (pintype "power_in"))
      (node (ref "U6") (pin "39_1") (pinfunction "GND_39_1") (pintype "power_in"))
      (node (ref "U6") (pin "39_2") (pinfunction "GND_39_2") (pintype "power_in"))
      (node (ref "U6") (pin "39_3") (pinfunction "GND_39_3") (pintype "power_in"))
      (node (ref "U6") (pin "39_4") (pinfunction "GND_39_4") (pintype "power_in"))
      (node (ref "U6") (pin "39_5") (pinfunction "GND_39_5") (pintype "power_in"))
      (node (ref "U6") (pin "39_6") (pinfunction "GND_39_6") (pintype "power_in"))
      (node (ref "U6") (pin "39_7") (pinfunction "GND_39_7") (pintype "power_in"))
      (node (ref "U6") (pin "39_8") (pinfunction "GND_39_8") (pintype "power_in"))
      (node (ref "U6") (pin "39_9") (pinfunction "GND_39_9") (pintype "power_in"))
      (node (ref "U7") (pin "8") (pinfunction "E_8") (pintype "passive"))
    )
    (net (code "33") (name "Net-(BT1-Pad1-)") (class "Default")
      (node (ref "BT1") (pin "1-") (pinfunction "1-_1-") (pintype "passive"))
      (node (ref "BT1") (pin "2+") (pinfunction "2+_2+") (pintype "passive"))
    )
    (net (code "34") (name "Net-(C4-Pad1)") (class "Default")
      (node (ref "C4") (pin "1") (pinfunction "1_1") (pintype "passive"))
      (node (ref "L1") (pin "2") (pinfunction "2_2") (pintype "passive"))
      (node (ref "L2") (pin "1") (pinfunction "1_1") (pintype "passive"))
    )
    (net (code "35") (name "Net-(D1-A)") (class "Default")
      (node (ref "D1") (pin "1") (pinfunction "A_1") (pintype "passive"))
      (node (ref "L1") (pin "1") (pinfunction "1_1") (pintype "passive"))
      (node (ref "U2") (pin "2") (pinfunction "Out_2") (pintype "passive"))
    )
    (net (code "36") (name "Net-(D2-Anode)") (class "Default")
      (node (ref "C10") (pin "2") (pinfunction "2_2") (pintype "passive"))
      (node (ref "D2") (pin "2") (pinfunction "Anode_2") (pintype "passive"))
      (node (ref "R6") (pin "2") (pinfunction "2_2") (pintype "passive"))
      (node (ref "U3") (pin "13") (pinfunction "6A_13") (pintype "input"))
    )
    (net (code "37") (name "Net-(D2-Cathode)") (class "Default")
      (node (ref "D2") (pin "1") (pinfunction "Cathode_1") (pintype "passive"))
      (node (ref "R6") (pin "1") (pinfunction "1_1") (pintype "passive"))
      (node (ref "U3") (pin "10") (pinfunction "5Y_10") (pintype "output"))
      (node (ref "U4") (pin "4") (pinfunction "DI_4") (pintype "input"))
    )
    (net (code "38") (name "Net-(D3-Anode)") (class "Default")
      (node (ref "D3") (pin "2") (pinfunction "Anode_2") (pintype "passive"))
      (node (ref "J1") (pin "1") (pinfunction "VCC_1") (pintype "power_in"))
      (node (ref "TVS4") (pin "1") (pinfunction "A_1") (pintype "passive"))
    )
    (net (code "39") (name "Net-(LED1-A)") (class "Default")
      (node (ref "LED1") (pin "2") (pinfunction "A_2") (pintype "passive"))
      (node (ref "R7") (pin "1") (pinfunction "1_1") (pintype "passive"))
    )
    (net (code "40") (name "Net-(LED2-A)") (class "Default")
      (node (ref "LED2") (pin "2") (pinfunction "A_2") (pintype "passive"))
      (node (ref "R8") (pin "1") (pinfunction "1_1") (pintype "passive"))
    )
    (net (code "41") (name "Net-(LED3-A)") (class "Default")
      (node (ref "LED3") (pin "2") (pinfunction "A_2") (pintype "passive"))
      (node (ref "R19") (pin "1") (pinfunction "1_1") (pintype "passive"))
    )
    (net (code "42") (name "Net-(LED3-K)") (class "Default")
      (node (ref "LED3") (pin "1") (pinfunction "K_1") (pintype "passive"))
      (node (ref "U6") (pin "13") (pinfunction "IO14_13") (pintype "bidirectional"))
    )
    (net (code "43") (name "Net-(LED4-A)") (class "Default")
      (node (ref "LED4") (pin "2") (pinfunction "A_2") (pintype "passive"))
      (node (ref "R20") (pin "1") (pinfunction "1_1") (pintype "passive"))
    )
    (net (code "44") (name "Net-(LED5-A)") (class "Default")
      (node (ref "LED5") (pin "2") (pinfunction "A_2") (pintype "passive"))
      (node (ref "R21") (pin "1") (pinfunction "1_1") (pintype "passive"))
    )
    (net (code "45") (name "Net-(LED6-A)") (class "Default")
      (node (ref "LED6") (pin "2") (pinfunction "A_2") (pintype "passive"))
      (node (ref "R22") (pin "1") (pinfunction "1_1") (pintype "passive"))
    )
    (net (code "46") (name "Net-(LED7-A)") (class "Default")
      (node (ref "LED7") (pin "2") (pinfunction "A_2") (pintype "passive"))
      (node (ref "R23") (pin "1") (pinfunction "1_1") (pintype "passive"))
    )
    (net (code "47") (name "Net-(P7-Pad1)") (class "Default")
      (node (ref "P7") (pin "1") (pinfunction "1_1") (pintype "passive"))
      (node (ref "RL1") (pin "NO") (pinfunction "NO_NO") (pintype "passive"))
    )
    (net (code "48") (name "Net-(P7-Pad2)") (class "Default")
      (node (ref "P7") (pin "2") (pinfunction "2_2") (pintype "passive"))
      (node (ref "RL1") (pin "COM") (pinfunction "COM_COM") (pintype "passive"))
    )
    (net (code "49") (name "Net-(P8-Pad1)") (class "Default")
      (node (ref "P8") (pin "1") (pinfunction "1_1") (pintype "passive"))
      (node (ref "RL2") (pin "NO") (pinfunction "NO_NO") (pintype "passive"))
    )
    (net (code "50") (name "Net-(P8-Pad2)") (class "Default")
      (node (ref "P8") (pin "2") (pinfunction "2_2") (pintype "passive"))
      (node (ref "RL2") (pin "COM") (pinfunction "COM_COM") (pintype "passive"))
    )
    (net (code "51") (name "Net-(P9-Pad1)") (class "Default")
      (node (ref "P9") (pin "1") (pinfunction "1_1") (pintype "passive"))
      (node (ref "RL3") (pin "NO") (pinfunction "NO_NO") (pintype "passive"))
    )
    (net (code "52") (name "Net-(P9-Pad2)") (class "Default")
      (node (ref "P9") (pin "2") (pinfunction "2_2") (pintype "passive"))
      (node (ref "RL3") (pin "COM") (pinfunction "COM_COM") (pintype "passive"))
    )
    (net (code "53") (name "Net-(P10-Pad1)") (class "Default")
      (node (ref "P10") (pin "1") (pinfunction "1_1") (pintype "passive"))
      (node (ref "RL4") (pin "NO") (pinfunction "NO_NO") (pintype "passive"))
    )
    (net (code "54") (name "Net-(P10-Pad2)") (class "Default")
      (node (ref "P10") (pin "2") (pinfunction "2_2") (pintype "passive"))
      (node (ref "RL4") (pin "COM") (pinfunction "COM_COM") (pintype "passive"))
    )
    (net (code "55") (name "Net-(PWR-A)") (class "Default")
      (node (ref "PWR") (pin "2") (pinfunction "A_2") (pintype "passive"))
      (node (ref "R4") (pin "1") (pinfunction "1_1") (pintype "passive"))
    )
    (net (code "56") (name "Net-(Q1-B)") (class "Default")
      (node (ref "Q1") (pin "1") (pinfunction "B_1") (pintype "passive"))
      (node (ref "R15") (pin "1") (pinfunction "1_1") (pintype "passive"))
    )
    (net (code "57") (name "Net-(Q2-B)") (class "Default")
      (node (ref "Q2") (pin "1") (pinfunction "B_1") (pintype "passive"))
      (node (ref "R16") (pin "1") (pinfunction "1_1") (pintype "passive"))
    )
    (net (code "58") (name "Net-(R13-Pad2)") (class "Default")
      (node (ref "R13") (pin "2") (pinfunction "2_2") (pintype "passive"))
      (node (ref "R14") (pin "1") (pinfunction "1_1") (pintype "passive"))
    )
    (net (code "59") (name "Net-(SW4-NO1)") (class "Default")
      (node (ref "BT1") (pin "1+") (pinfunction "1+_1+") (pintype "passive"))
      (node (ref "SW4") (pin "3") (pinfunction "NO1_3") (pintype "passive"))
    )
    (net (code "60") (name "Net-(U1-BYPASS)") (class "Default")
      (node (ref "C2") (pin "1") (pinfunction "1_1") (pintype "passive"))
      (node (ref "U1") (pin "4") (pinfunction "BYPASS_4") (pintype "bidirectional"))
    )
    (net (code "61") (name "Net-(U1-ON{slash}~{OFF})") (class "Default")
      (node (ref "R1") (pin "1") (pinfunction "1_1") (pintype "passive"))
      (node (ref "U1") (pin "3") (pinfunction "ON/~{OFF}_3") (pintype "input"))
    )
    (net (code "62") (name "Net-(U3-1Y)") (class "Default")
      (node (ref "R7") (pin "2") (pinfunction "2_2") (pintype "passive"))
      (node (ref "U3") (pin "11") (pinfunction "5A_11") (pintype "input"))
      (node (ref "U3") (pin "2") (pinfunction "1Y_2") (pintype "output"))
    )
    (net (code "63") (name "Net-(U3-2A)") (class "Default")
      (node (ref "R8") (pin "2") (pinfunction "2_2") (pintype "passive"))
      (node (ref "U3") (pin "3") (pinfunction "2A_3") (pintype "input"))
      (node (ref "U3") (pin "8") (pinfunction "4Y_8") (pintype "output"))
    )
    (net (code "64") (name "Net-(U3-6Y)") (class "Default")
      (node (ref "U3") (pin "12") (pinfunction "6Y_12") (pintype "output"))
      (node (ref "U4") (pin "2") (pinfunction "~{RE}_2") (pintype "input"))
      (node (ref "U4") (pin "3") (pinfunction "DE_3") (pintype "input"))
    )
    (net (code "65") (name "Net-(U5-XI)") (class "Default")
      (node (ref "C14") (pin "1") (pinfunction "1_1") (pintype "passive"))
      (node (ref "U5") (pin "7") (pinfunction "XI_7") (pintype "input"))
      (node (ref "Y1") (pin "2") (pinfunction "2_2") (pintype "passive"))
    )
    (net (code "66") (name "Net-(U5-XO)") (class "Default")
      (node (ref "C13") (pin "1") (pinfunction "1_1") (pintype "passive"))
      (node (ref "U5") (pin "8") (pinfunction "XO_8") (pintype "output"))
      (node (ref "Y1") (pin "1") (pinfunction "1_1") (pintype "passive"))
    )
    (net (code "67") (name "V_BAT") (class "Default")
      (node (ref "C1") (pin "1") (pinfunction "1_1") (pintype "passive"))
      (node (ref "J2") (pin "1") (pinfunction "1_1") (pintype "passive"))
      (node (ref "P2") (pin "2") (pinfunction "2_2") (pintype "passive"))
      (node (ref "R1") (pin "2") (pinfunction "2_2") (pintype "passive"))
      (node (ref "SW4") (pin "2") (pinfunction "COMMON1_2") (pintype "passive"))
      (node (ref "U1") (pin "1") (pinfunction "VIN_1") (pintype "input"))
      (node (ref "U2") (pin "1") (pinfunction "Vin_1") (pintype "passive"))
    )
    (net (code "68") (name "unconnected-(GDT1-Pad3)") (class "Default")
      (node (ref "GDT1") (pin "3") (pinfunction "3_3") (pintype "passive"))
    )
    (net (code "69") (name "unconnected-(H1-Pad1)") (class "Default")
      (node (ref "H1") (pin "1") (pinfunction "1_1") (pintype "passive"))
    )
    (net (code "70") (name "unconnected-(H2-Pad1)") (class "Default")
      (node (ref "H2") (pin "1") (pinfunction "1_1") (pintype "passive"))
    )
    (net (code "71") (name "unconnected-(H3-Pad1)") (class "Default")
      (node (ref "H3") (pin "1") (pinfunction "1_1") (pintype "passive"))
    )
    (net (code "72") (name "unconnected-(H4-Pad1)") (class "Default")
      (node (ref "H4") (pin "1") (pinfunction "1_1") (pintype "passive"))
    )
    (net (code "73") (name "unconnected-(J1-ID-Pad4)") (class "Default")
      (node (ref "J1") (pin "4") (pinfunction "ID_4") (pintype "bidirectional"))
    )
    (net (code "74") (name "unconnected-(RL1-PadNC)") (class "Default")
      (node (ref "RL1") (pin "NC") (pinfunction "NC_NC") (pintype "passive"))
    )
    (net (code "75") (name "unconnected-(RL2-PadNC)") (class "Default")
      (node (ref "RL2") (pin "NC") (pinfunction "NC_NC") (pintype "passive"))
    )
    (net (code "76") (name "unconnected-(RL3-PadNC)") (class "Default")
      (node (ref "RL3") (pin "NC") (pinfunction "NC_NC") (pintype "passive"))
    )
    (net (code "77") (name "unconnected-(RL4-PadNC)") (class "Default")
      (node (ref "RL4") (pin "NC") (pinfunction "NC_NC") (pintype "passive"))
    )
    (net (code "78") (name "unconnected-(SW4-NC1-Pad1)") (class "Default")
      (node (ref "SW4") (pin "1") (pinfunction "NC1_1") (pintype "passive"))
    )
    (net (code "79") (name "unconnected-(U2-TAB-Pad6)") (class "Default")
      (node (ref "U2") (pin "6") (pinfunction "TAB_6") (pintype "passive"))
    )
    (net (code "80") (name "unconnected-(U3-3A-Pad5)") (class "Default")
      (node (ref "U3") (pin "5") (pinfunction "3A_5") (pintype "input"))
    )
    (net (code "81") (name "unconnected-(U3-3Y-Pad6)") (class "Default")
      (node (ref "U3") (pin "6") (pinfunction "3Y_6") (pintype "output"))
    )
    (net (code "82") (name "unconnected-(U5-CTS#-Pad9)") (class "Default")
      (node (ref "U5") (pin "9") (pinfunction "CTS#_9") (pintype "input"))
    )
    (net (code "83") (name "unconnected-(U5-DCD#-Pad12)") (class "Default")
      (node (ref "U5") (pin "12") (pinfunction "DCD#_12") (pintype "input"))
    )
    (net (code "84") (name "unconnected-(U5-DSR#-Pad10)") (class "Default")
      (node (ref "U5") (pin "10") (pinfunction "DSR#_10") (pintype "input"))
    )
    (net (code "85") (name "unconnected-(U5-RI#-Pad11)") (class "Default")
      (node (ref "U5") (pin "11") (pinfunction "RI#_11") (pintype "input"))
    )
    (net (code "86") (name "unconnected-(U5-RS232-Pad15)") (class "Default")
      (node (ref "U5") (pin "15") (pinfunction "RS232_15") (pintype "input"))
    )
    (net (code "87") (name "unconnected-(U5-V3-Pad4)") (class "Default")
      (node (ref "U5") (pin "4") (pinfunction "V3_4") (pintype "power_in"))
    )
    (net (code "88") (name "unconnected-(U6-IO2-Pad24)") (class "Default")
      (node (ref "U6") (pin "24") (pinfunction "IO2_24") (pintype "bidirectional"))
    )
    (net (code "89") (name "unconnected-(U6-IO12-Pad14)") (class "Default")
      (node (ref "U6") (pin "14") (pinfunction "IO12_14") (pintype "bidirectional"))
    )
    (net (code "90") (name "unconnected-(U6-IO13-Pad16)") (class "Default")
      (node (ref "U6") (pin "16") (pinfunction "IO13_16") (pintype "bidirectional"))
    )
    (net (code "91") (name "unconnected-(U6-IO15-Pad23)") (class "Default")
      (node (ref "U6") (pin "23") (pinfunction "IO15_23") (pintype "bidirectional"))
    )
    (net (code "92") (name "unconnected-(U6-IO22-Pad36)") (class "Default")
      (node (ref "U6") (pin "36") (pinfunction "IO22_36") (pintype "bidirectional"))
    )
    (net (code "93") (name "unconnected-(U6-IO23-Pad37)") (class "Default")
      (node (ref "U6") (pin "37") (pinfunction "IO23_37") (pintype "bidirectional"))
    )
    (net (code "94") (name "unconnected-(U6-IO25-Pad10)") (class "Default")
      (node (ref "U6") (pin "10") (pinfunction "IO25_10") (pintype "bidirectional"))
    )
    (net (code "95") (name "unconnected-(U6-IO26-Pad11)") (class "Default")
      (node (ref "U6") (pin "11") (pinfunction "IO26_11") (pintype "bidirectional"))
    )
    (net (code "96") (name "unconnected-(U6-IO33-Pad9)") (class "Default")
      (node (ref "U6") (pin "9") (pinfunction "IO33_9") (pintype "bidirectional"))
    )
    (net (code "97") (name "unconnected-(U6-IO35-Pad7)") (class "Default")
      (node (ref "U6") (pin "7") (pinfunction "IO35_7") (pintype "input"))
    )
    (net (code "98") (name "unconnected-(U6-IO36{slash}SENSOR_VP-Pad4)") (class "Default")
      (node (ref "U6") (pin "4") (pinfunction "IO36/SENSOR_VP_4") (pintype "input"))
    )
    (net (code "99") (name "unconnected-(U6-IO39{slash}SENSOR_VN-Pad5)") (class "Default")
      (node (ref "U6") (pin "5") (pinfunction "IO39/SENSOR_VN_5") (pintype "input"))
    )
    (net (code "100") (name "unconnected-(U6-NC-Pad32)") (class "Default")
      (node (ref "U6") (pin "32") (pinfunction "NC_32") (pintype "passive"))
    )
    (net (code "101") (name "unconnected-(U6-SCL{slash}CLK-Pad20)") (class "Default")
      (node (ref "U6") (pin "20") (pinfunction "SCL/CLK_20") (pintype "bidirectional"))
    )
    (net (code "102") (name "unconnected-(U6-SCS{slash}CMD-Pad19)") (class "Default")
      (node (ref "U6") (pin "19") (pinfunction "SCS/CMD_19") (pintype "bidirectional"))
    )
    (net (code "103") (name "unconnected-(U6-SD1{slash}SD1-Pad22)") (class "Default")
      (node (ref "U6") (pin "22") (pinfunction "SD1/SD1_22") (pintype "bidirectional"))
    )
    (net (code "104") (name "unconnected-(U6-SDO{slash}SD0-Pad21)") (class "Default")
      (node (ref "U6") (pin "21") (pinfunction "SDO/SD0_21") (pintype "bidirectional"))
    )
    (net (code "105") (name "unconnected-(U6-SHD{slash}SD2-Pad17)") (class "Default")
      (node (ref "U6") (pin "17") (pinfunction "SHD/SD2_17") (pintype "bidirectional"))
    )
    (net (code "106") (name "unconnected-(U6-SWP{slash}SD3-Pad18)") (class "Default")
      (node (ref "U6") (pin "18") (pinfunction "SWP/SD3_18") (pintype "bidirectional"))
    )
    (net (code "107") (name "unconnected-(U7-1B-Pad1)") (class "Default")
      (node (ref "U7") (pin "1") (pinfunction "1B_1") (pintype "passive"))
    )
    (net (code "108") (name "unconnected-(U7-1C-Pad16)") (class "Default")
      (node (ref "U7") (pin "16") (pinfunction "1C_16") (pintype "passive"))
    )
    (net (code "109") (name "unconnected-(U7-2B-Pad2)") (class "Default")
      (node (ref "U7") (pin "2") (pinfunction "2B_2") (pintype "passive"))
    )
    (net (code "110") (name "unconnected-(U7-2C-Pad15)") (class "Default")
      (node (ref "U7") (pin "15") (pinfunction "2C_15") (pintype "passive"))
    )
    (net (code "111") (name "unconnected-(U7-3B-Pad3)") (class "Default")
      (node (ref "U7") (pin "3") (pinfunction "3B_3") (pintype "passive"))
    )
    (net (code "112") (name "unconnected-(U7-3C-Pad14)") (class "Default")
      (node (ref "U7") (pin "14") (pinfunction "3C_14") (pintype "passive"))
    )
  )
)
